# controller.net
KiCad netlist of a schematic drawn in EAGLE
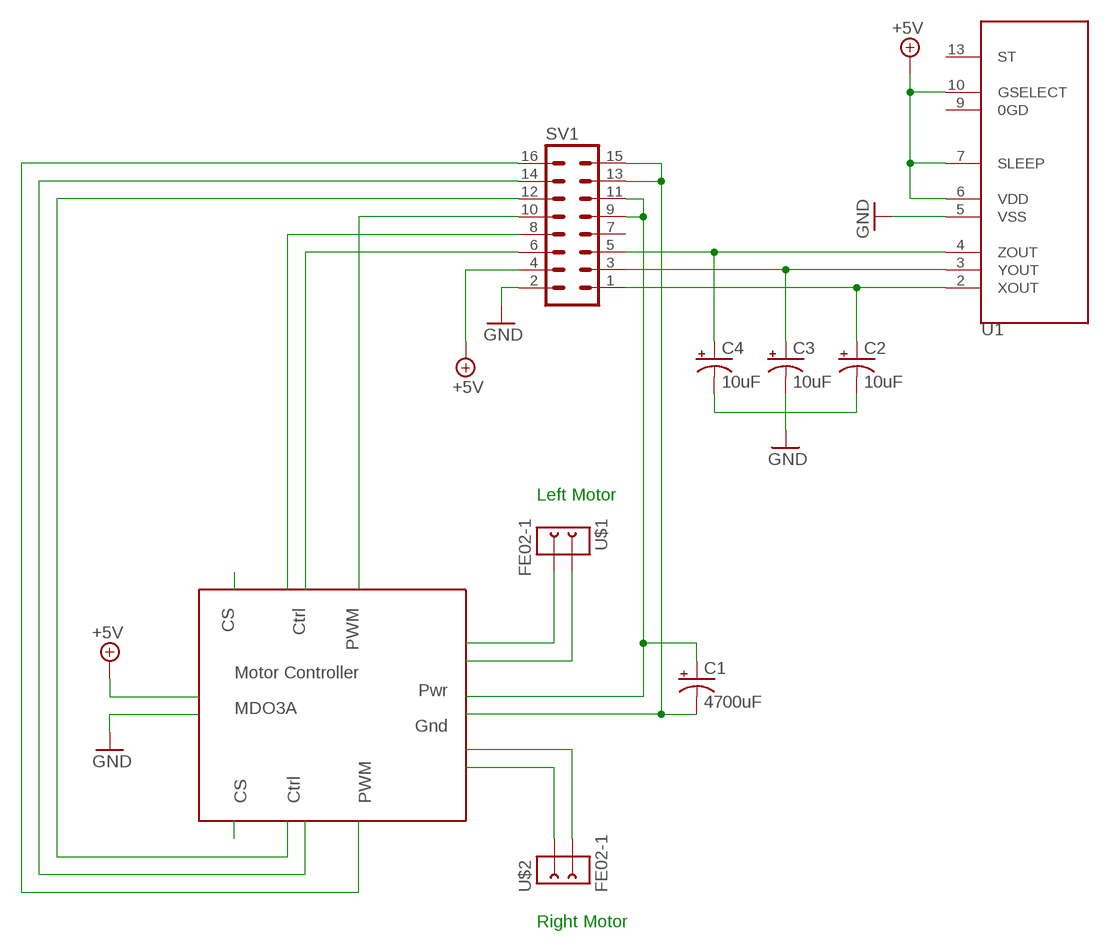
[diagram p0: schematic, sheet 1]

(export (version "E")
  (design (tool "Eeschema 10.0.6"))
  (components
    (comp (ref "C1")
      (value "4700uF")
      (footprint "eagle-import:CPOL-RADIAL-100UF-25V")
      (libsource (lib "eagle-import") (part "CAP_POLPTH1"))
    )
    (comp (ref "C2")
      (value "10uF")
      (footprint "eagle-import:CPOL-RADIAL-100UF-25V")
      (libsource (lib "eagle-import") (part "CAP_POLPTH1"))
    )
    (comp (ref "C3")
      (value "10uF")
      (footprint "eagle-import:CPOL-RADIAL-100UF-25V")
      (libsource (lib "eagle-import") (part "CAP_POLPTH1"))
    )
    (comp (ref "C4")
      (value "10uF")
      (footprint "eagle-import:CPOL-RADIAL-100UF-25V")
      (libsource (lib "eagle-import") (part "CAP_POLPTH1"))
    )
    (comp (ref "SV1")
      (value "MA08-2")
      (footprint "eagle-import:MA08-2")
      (libsource (lib "eagle-import") (part "MA08-2"))
    )
    (comp (ref "U$1")
      (value "FE02-1")
      (footprint "eagle-import:FE02-1")
      (libsource (lib "eagle-import") (part "FE02-1"))
    )
    (comp (ref "U$2")
      (value "FE02-1")
      (footprint "eagle-import:FE02-1")
      (libsource (lib "eagle-import") (part "FE02-1"))
    )
    (comp (ref "U1")
      (value "MMA7361")
      (footprint "eagle-import:LGA14")
      (libsource (lib "eagle-import") (part "MMA7361"))
    )
  )
  (nets
    (net (code "1") (name "+5V") (class "Default")
      (node (ref "SV1") (pin "4") (pinfunction "4_4") (pintype "passive"))
      (node (ref "U1") (pin "10") (pinfunction "GSELECT_10") (pintype "bidirectional"))
      (node (ref "U1") (pin "6") (pinfunction "VDD_6") (pintype "bidirectional"))
      (node (ref "U1") (pin "7") (pinfunction "SLEEP_7") (pintype "bidirectional"))
    )
    (net (code "2") (name "GND") (class "Default")
      (node (ref "C2") (pin "2") (pinfunction "-_2") (pintype "passive"))
      (node (ref "C3") (pin "2") (pinfunction "-_2") (pintype "passive"))
      (node (ref "C4") (pin "2") (pinfunction "-_2") (pintype "passive"))
      (node (ref "SV1") (pin "2") (pinfunction "2_2") (pintype "passive"))
      (node (ref "U1") (pin "5") (pinfunction "VSS_5") (pintype "bidirectional"))
    )
    (net (code "3") (name "Net-(C1-+)") (class "Default")
      (node (ref "C1") (pin "1") (pinfunction "+_1") (pintype "passive"))
      (node (ref "SV1") (pin "11") (pinfunction "11_11") (pintype "passive"))
      (node (ref "SV1") (pin "9") (pinfunction "9_9") (pintype "passive"))
    )
    (net (code "4") (name "Net-(C1--)") (class "Default")
      (node (ref "C1") (pin "2") (pinfunction "-_2") (pintype "passive"))
      (node (ref "SV1") (pin "13") (pinfunction "13_13") (pintype "passive"))
      (node (ref "SV1") (pin "15") (pinfunction "15_15") (pintype "passive"))
    )
    (net (code "5") (name "Net-(C2-+)") (class "Default")
      (node (ref "C2") (pin "1") (pinfunction "+_1") (pintype "passive"))
      (node (ref "SV1") (pin "1") (pinfunction "1_1") (pintype "passive"))
      (node (ref "U1") (pin "2") (pinfunction "XOUT_2") (pintype "bidirectional"))
    )
    (net (code "6") (name "Net-(C3-+)") (class "Default")
      (node (ref "C3") (pin "1") (pinfunction "+_1") (pintype "passive"))
      (node (ref "SV1") (pin "3") (pinfunction "3_3") (pintype "passive"))
      (node (ref "U1") (pin "3") (pinfunction "YOUT_3") (pintype "bidirectional"))
    )
    (net (code "7") (name "Net-(C4-+)") (class "Default")
      (node (ref "C4") (pin "1") (pinfunction "+_1") (pintype "passive"))
      (node (ref "SV1") (pin "5") (pinfunction "5_5") (pintype "passive"))
      (node (ref "U1") (pin "4") (pinfunction "ZOUT_4") (pintype "bidirectional"))
    )
    (net (code "8") (name "unconnected-(SV1-Pad6)") (class "Default")
      (node (ref "SV1") (pin "6") (pinfunction "6_6") (pintype "passive"))
    )
    (net (code "9") (name "unconnected-(SV1-Pad7)") (class "Default")
      (node (ref "SV1") (pin "7") (pinfunction "7_7") (pintype "passive"))
    )
    (net (code "10") (name "unconnected-(SV1-Pad8)") (class "Default")
      (node (ref "SV1") (pin "8") (pinfunction "8_8") (pintype "passive"))
    )
    (net (code "11") (name "unconnected-(SV1-Pad10)") (class "Default")
      (node (ref "SV1") (pin "10") (pinfunction "10_10") (pintype "passive"))
    )
    (net (code "12") (name "unconnected-(SV1-Pad12)") (class "Default")
      (node (ref "SV1") (pin "12") (pinfunction "12_12") (pintype "passive"))
    )
    (net (code "13") (name "unconnected-(SV1-Pad14)") (class "Default")
      (node (ref "SV1") (pin "14") (pinfunction "14_14") (pintype "passive"))
    )
    (net (code "14") (name "unconnected-(SV1-Pad16)") (class "Default")
      (node (ref "SV1") (pin "16") (pinfunction "16_16") (pintype "passive"))
    )
    (net (code "15") (name "unconnected-(U$1-PadP$1)") (class "Default")
      (node (ref "U$1") (pin "P$1") (pinfunction "P$1_P$1") (pintype "bidirectional"))
    )
    (net (code "16") (name "unconnected-(U$1-PadP$2)") (class "Default")
      (node (ref "U$1") (pin "P$2") (pinfunction "P$2_P$2") (pintype "bidirectional"))
    )
    (net (code "17") (name "unconnected-(U$2-PadP$1)") (class "Default")
      (node (ref "U$2") (pin "P$1") (pinfunction "P$1_P$1") (pintype "bidirectional"))
    )
    (net (code "18") (name "unconnected-(U$2-PadP$2)") (class "Default")
      (node (ref "U$2") (pin "P$2") (pinfunction "P$2_P$2") (pintype "bidirectional"))
    )
    (net (code "19") (name "unconnected-(U1-0GD-Pad9)") (class "Default")
      (node (ref "U1") (pin "9") (pinfunction "0GD_9") (pintype "bidirectional"))
    )
    (net (code "20") (name "unconnected-(U1-ST-Pad13)") (class "Default")
      (node (ref "U1") (pin "13") (pinfunction "ST_13") (pintype "bidirectional"))
    )
  )
)
